# Python_Auxiliary.net
KiCad netlist of a schematic drawn in Altium Designer
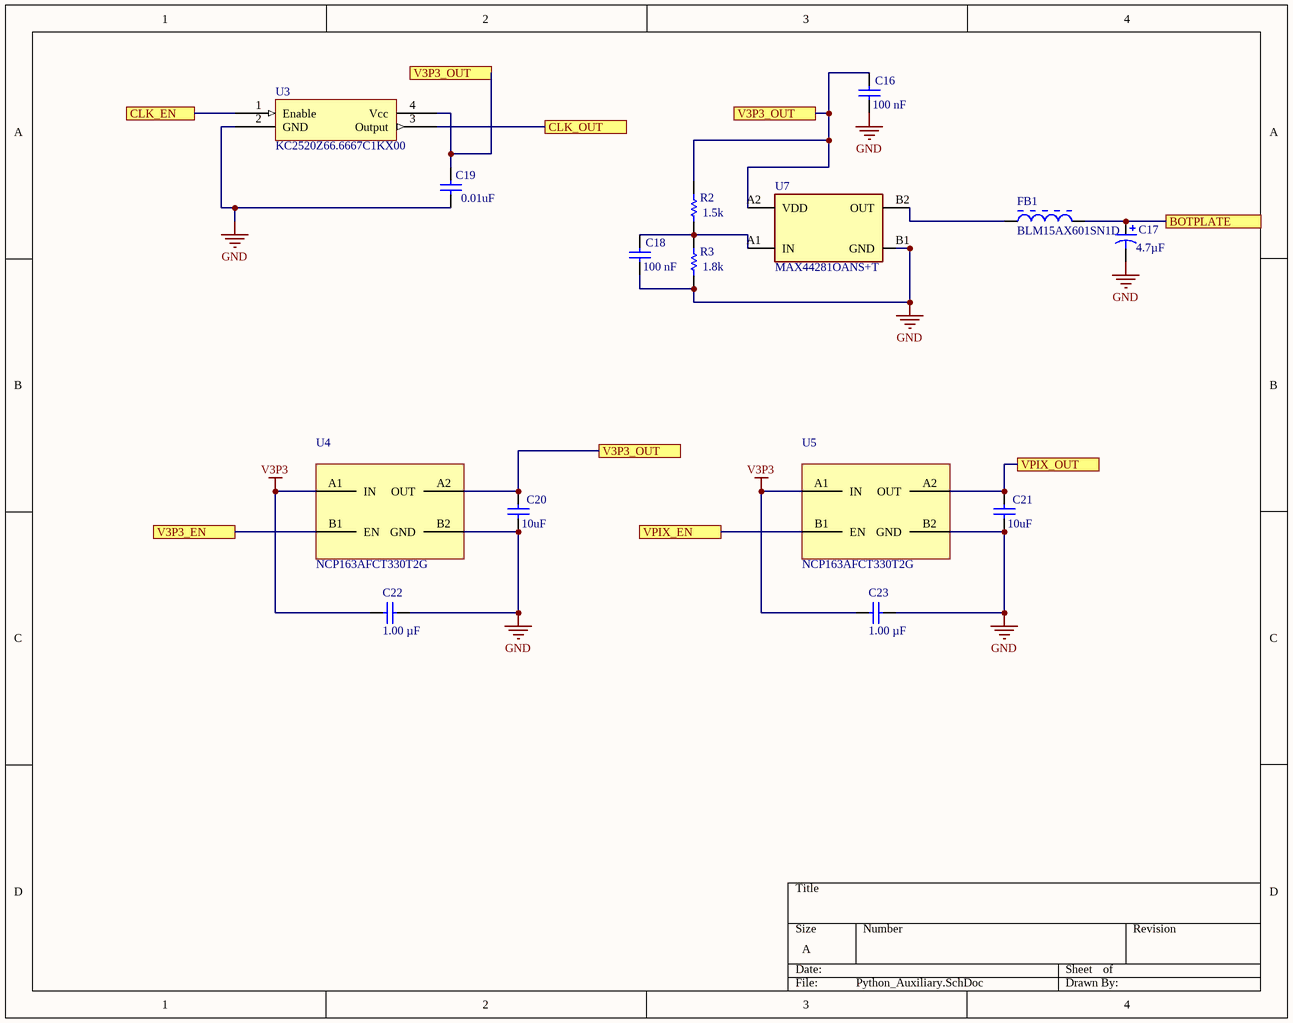
[diagram p0: Python_Auxiliary.SchDoc]

(export (version "E")
  (design (tool "Eeschema 10.0.6"))
  (components
    (comp (ref "C16")
      (value "GRM033C71C104KE14D")
      (footprint "PCB-v6eq6etc9p7u7qdkgnno-1")
      (description "0.1 µF ±10% 16V Ceramic Capacitor X7S 0201 (0603 Metric)")
      (fields (field (name "CAPACITANCE") "100 nF"))
      (libsource (lib "Python_Imaging_1") (part "CMP-cc290632c88a13ee-3"))
    )
    (comp (ref "C17")
      (value "F981A475MUALZT")
      (footprint "PCB-t0dwbiosd2m6unyihqym-1")
      (description "4.7 µF Molded Tantalum Capacitors 10 V 0402 (1005 Metric) -")
      (fields (field (name "CAPACITANCE") "4.7µF"))
      (libsource (lib "Python_Imaging_1") (part "SYM-b7737c8c1b6d68b4-1"))
    )
    (comp (ref "C18")
      (value "GRM033C71C104KE14D")
      (footprint "PCB-v6eq6etc9p7u7qdkgnno-1")
      (description "0.1 µF ±10% 16V Ceramic Capacitor X7S 0201 (0603 Metric)")
      (fields (field (name "CAPACITANCE") "100 nF"))
      (libsource (lib "Python_Imaging_1") (part "CMP-cc290632c88a13ee-3"))
    )
    (comp (ref "C19")
      (value "GRM033R71A103KA01D")
      (footprint "PCB-v6eq6etc9p7u7qdkgnno-1")
      (description "10000 pF ±10% 10V Ceramic Capacitor X7R 0201 (0603 Metric)")
      (fields (field (name "CAPACITANCE") "0.01uF"))
      (libsource (lib "Python_Imaging_1") (part "CMP-19299660-4"))
    )
    (comp (ref "C20")
      (value "GRM155R61A106ME11D")
      (footprint "PCB-uspfzztrpe7hn2xlyjz9-1")
      (description "10 µF ±20% 10V Ceramic Capacitor X5R 0402 (1005 Metric)")
      (fields (field (name "CAPACITANCE") "10uF"))
      (libsource (lib "Python_Imaging_1") (part "CMP-eacb22ede71a350c-8"))
    )
    (comp (ref "C21")
      (value "GRM155R61A106ME11D")
      (footprint "PCB-uspfzztrpe7hn2xlyjz9-1")
      (description "10 µF ±20% 10V Ceramic Capacitor X5R 0402 (1005 Metric)")
      (fields (field (name "CAPACITANCE") "10uF"))
      (libsource (lib "Python_Imaging_1") (part "CMP-eacb22ede71a350c-8"))
    )
    (comp (ref "C22")
      (value "GRM033R60J105MEA2D")
      (footprint "PCB-v6eq6etc9p7u7qdkgnno-1")
      (description "1 µF ±20% 6.3V Ceramic Capacitor X5R 0201 (0603 Metric)")
      (fields (field (name "CAPACITANCE") "1.00 µF"))
      (libsource (lib "Python_Imaging_1") (part "CMP-7dcab586fd61a20d-5"))
    )
    (comp (ref "C23")
      (value "GRM033R60J105MEA2D")
      (footprint "PCB-v6eq6etc9p7u7qdkgnno-1")
      (description "1 µF ±20% 6.3V Ceramic Capacitor X5R 0201 (0603 Metric)")
      (fields (field (name "CAPACITANCE") "1.00 µF"))
      (libsource (lib "Python_Imaging_1") (part "CMP-7dcab586fd61a20d-5"))
    )
    (comp (ref "FB1")
      (value "BLM15AX601SN1D")
      (footprint "MURA-BLM15-CHIP-2_V")
      (description "600 Ohms @ 100 MHz 1 - Ferrite Bead 0402 (1005 Metric) 500mA 340mOhm")
      (libsource (lib "Python_Imaging_1") (part "MURA-FB-2"))
    )
    (comp (ref "R2")
      (value "ERA-1AEB152C")
      (footprint "PCB-7g93mzch2qc2q3jid3ok-1")
      (description "1.5 kOhms ±0.1% 0.05W, 1/20W Chip Resistor 0201 (0603 Metric) - Thin Film")
      (fields (field (name "RESISTANCE") "1.5k"))
      (libsource (lib "Python_Imaging_1") (part "CMP-1848326-4"))
    )
    (comp (ref "R3")
      (value "CRCW02011K80JNED")
      (footprint "PCB-7g93mzch2qc2q3jid3ok-1")
      (description "1.8 kOhms ±5% 0.05W, 1/20W Chip Resistor 0201 (0603 Metric) - Thick Film")
      (fields (field (name "RESISTANCE") "1.8k"))
      (libsource (lib "Python_Imaging_1") (part "CMP-1848326-4"))
    )
    (comp (ref "U3")
      (value "KC2520Z66.6667C1KX00")
      (footprint "ASD")
      (description "66.667 MHz XO (Standard) CMOS Oscillator 1.71V ~ 3.63V Standby (Power Down) 4-SMD, No Lead")
      (libsource (lib "Schematic_Components") (part "ASD oscillator"))
    )
    (comp (ref "U4")
      (value "NCP163AFCT330T2G")
      (footprint "PCB-ng8273kv6qqz2xsov2q1-1")
      (description "Linear Voltage Regulator IC Positive Fixed 1 Output 250mA 4-WLCSP (0.64x0.64)")
      (libsource (lib "Python_Imaging_1") (part "SYM-c6890ab21004194e-1"))
    )
    (comp (ref "U5")
      (value "NCP163AFCT330T2G")
      (footprint "PCB-ng8273kv6qqz2xsov2q1-1")
      (description "Linear Voltage Regulator IC Positive Fixed 1 Output 250mA 4-WLCSP (0.64x0.64)")
      (libsource (lib "Python_Imaging_1") (part "SYM-c6890ab21004194e-1"))
    )
    (comp (ref "U7")
      (value "MAX44281OANS+T")
      (footprint "FP-N40A0-1-MFG")
      (description "General Purpose Amplifier 1 Circuit Rail-to-Rail 4-WLP (0.84x0.84)")
      (libsource (lib "Altium Content Vault") (part "997df25dfb95172ee543318bfba6319"))
    )
  )
  (nets
    (net (code "1") (name "/BOTPLATE") (class "Default")
      (node (ref "C17") (pin "1") (pinfunction "1_1") (pintype "passive"))
      (node (ref "FB1") (pin "2") (pinfunction "2_2") (pintype "passive"))
    )
    (net (code "2") (name "/CLK_EN") (class "Default")
      (node (ref "U3") (pin "1") (pinfunction "Enable_1") (pintype "input"))
    )
    (net (code "3") (name "/CLK_OUT") (class "Default")
      (node (ref "U3") (pin "3") (pinfunction "Output_3") (pintype "output"))
    )
    (net (code "4") (name "/V3P3_EN") (class "Default")
      (node (ref "U4") (pin "B1") (pinfunction "EN_B1") (pintype "passive"))
    )
    (net (code "5") (name "/V3P3_OUT") (class "Default")
      (node (ref "C16") (pin "2") (pinfunction "2_2") (pintype "passive"))
      (node (ref "C19") (pin "2") (pinfunction "2_2") (pintype "passive"))
      (node (ref "C20") (pin "1") (pinfunction "1_1") (pintype "passive"))
      (node (ref "R2") (pin "2") (pinfunction "2_2") (pintype "passive"))
      (node (ref "U3") (pin "4") (pinfunction "Vcc_4") (pintype "power_in"))
      (node (ref "U4") (pin "A2") (pinfunction "OUT_A2") (pintype "passive"))
      (node (ref "U7") (pin "A2") (pinfunction "VDD_A2") (pintype "power_in"))
    )
    (net (code "6") (name "/VPIX_EN") (class "Default")
      (node (ref "U5") (pin "B1") (pinfunction "EN_B1") (pintype "passive"))
    )
    (net (code "7") (name "/VPIX_OUT") (class "Default")
      (node (ref "C21") (pin "1") (pinfunction "1_1") (pintype "passive"))
      (node (ref "U5") (pin "A2") (pinfunction "OUT_A2") (pintype "passive"))
    )
    (net (code "8") (name "GND") (class "Default")
      (node (ref "C16") (pin "1") (pinfunction "1_1") (pintype "passive"))
      (node (ref "C17") (pin "2") (pinfunction "2_2") (pintype "passive"))
      (node (ref "C18") (pin "1") (pinfunction "1_1") (pintype "passive"))
      (node (ref "C19") (pin "1") (pinfunction "1_1") (pintype "passive"))
      (node (ref "C20") (pin "2") (pinfunction "2_2") (pintype "passive"))
      (node (ref "C21") (pin "2") (pinfunction "2_2") (pintype "passive"))
      (node (ref "C22") (pin "1") (pinfunction "1_1") (pintype "passive"))
      (node (ref "C23") (pin "1") (pinfunction "1_1") (pintype "passive"))
      (node (ref "R3") (pin "1") (pinfunction "1_1") (pintype "passive"))
      (node (ref "U3") (pin "2") (pinfunction "GND_2") (pintype "power_in"))
      (node (ref "U4") (pin "B2") (pinfunction "GND_B2") (pintype "passive"))
      (node (ref "U5") (pin "B2") (pinfunction "GND_B2") (pintype "passive"))
      (node (ref "U7") (pin "B1") (pinfunction "GND_B1") (pintype "power_in"))
    )
    (net (code "9") (name "Net-(U7-IN)") (class "Default")
      (node (ref "C18") (pin "2") (pinfunction "2_2") (pintype "passive"))
      (node (ref "R2") (pin "1") (pinfunction "1_1") (pintype "passive"))
      (node (ref "R3") (pin "2") (pinfunction "2_2") (pintype "passive"))
      (node (ref "U7") (pin "A1") (pinfunction "IN_A1") (pintype "tri_state"))
    )
    (net (code "10") (name "Net-(U7-OUT)") (class "Default")
      (node (ref "FB1") (pin "1") (pinfunction "1_1") (pintype "passive"))
      (node (ref "U7") (pin "B2") (pinfunction "OUT_B2") (pintype "passive"))
    )
    (net (code "11") (name "V3P3") (class "Default")
      (node (ref "C22") (pin "2") (pinfunction "2_2") (pintype "passive"))
      (node (ref "C23") (pin "2") (pinfunction "2_2") (pintype "passive"))
      (node (ref "U4") (pin "A1") (pinfunction "IN_A1") (pintype "passive"))
      (node (ref "U5") (pin "A1") (pinfunction "IN_A1") (pintype "passive"))
    )
  )
)
